# DD2090_4CAM_FFC_Power_Supply.net
KiCad netlist of a schematic drawn in Altium Designer
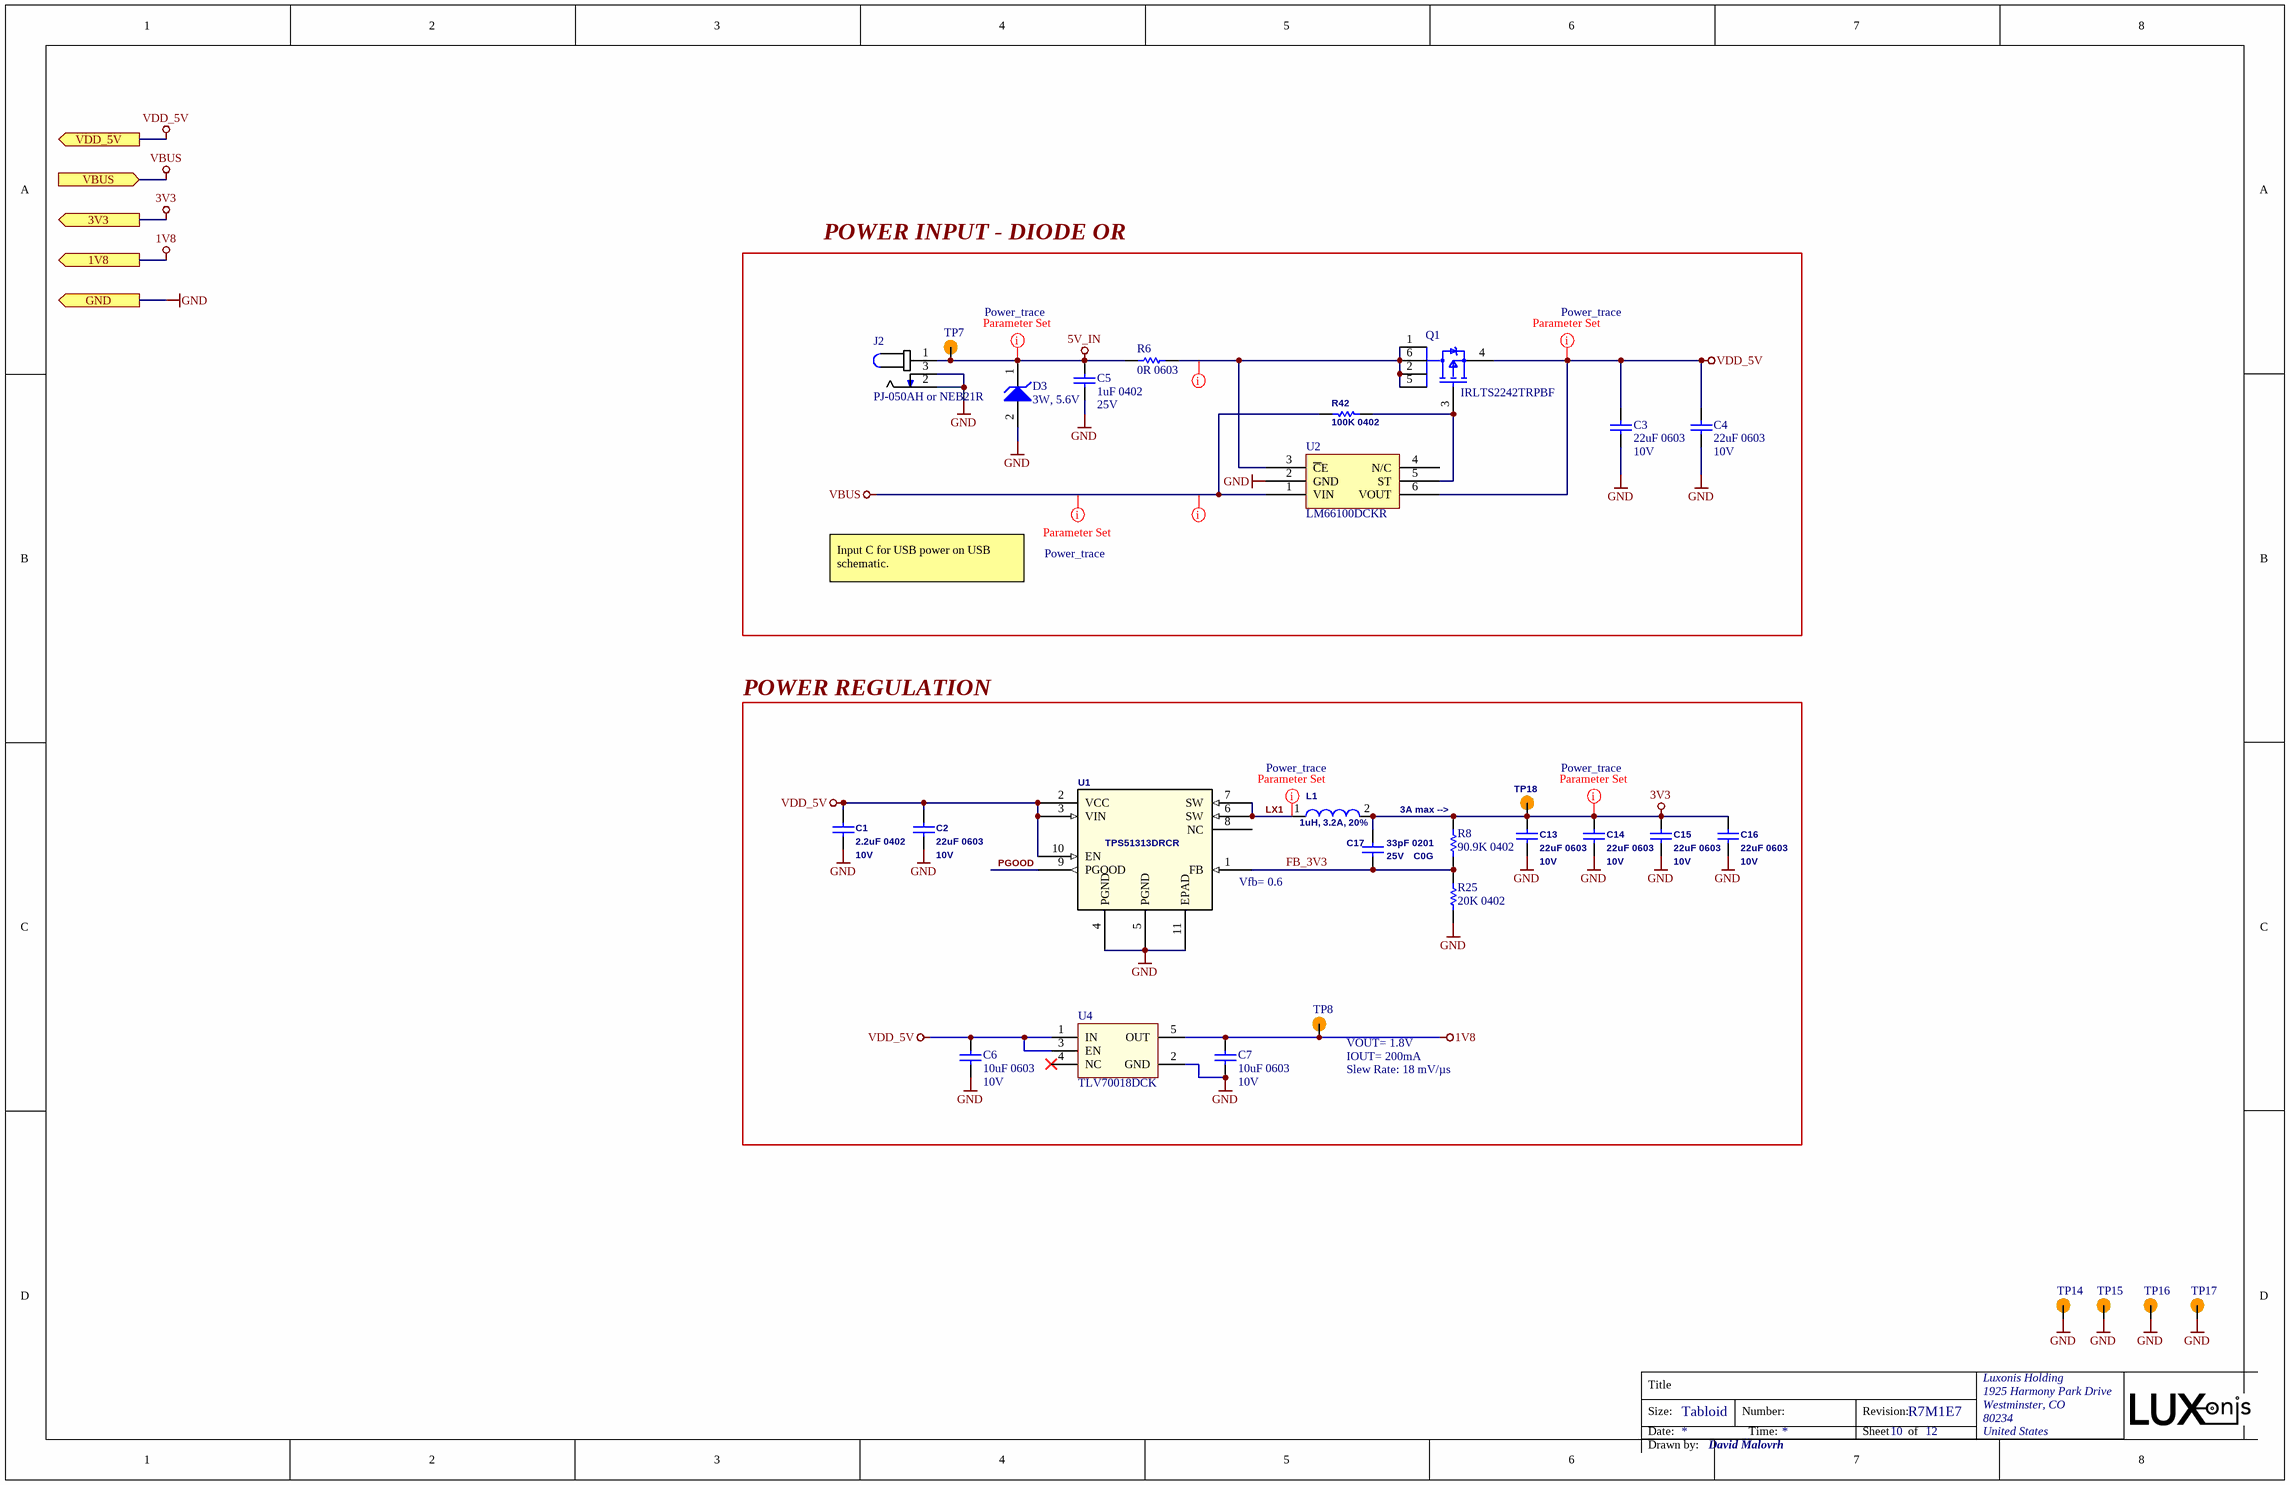
[diagram p0: DD2090_4CAM_FFC_Power_Supply.SchDoc]

(export (version "E")
  (design (tool "Eeschema 10.0.6"))
  (components
    (comp (ref "C1")
      (value "2.2uF 0402")
      (footprint "CAP_Altium_Vault_Generic:CAPC0402(1005)70_L")
      (description "CAP CER 2.2UF 10V X5R 0402 10%")
      (fields (field (name "TOLERANCE") "10%") (field (name "VOLTAGE RATING") "10V"))
      (libsource (lib "LuxonisMaster") (part "GRM155R61A225KE95D"))
    )
    (comp (ref "C2")
      (value "22uF 0603")
      (footprint "CAP_Altium_Vault_Generic:CAPC0603(1608)100_L")
      (description "CAP CER 22UF 10V X5R 0603 20%")
      (fields (field (name "TOLERANCE") "20%") (field (name "VOLTAGE RATING") "10V"))
      (libsource (lib "LuxonisMaster") (part "GRM188R61A226ME15D"))
    )
    (comp (ref "C3")
      (value "22uF 0603")
      (footprint "CAP_Altium_Vault_Generic:CAPC0603(1608)100_N")
      (description "CAP CER 22UF 10V X5R 0603 20%")
      (fields (field (name "TOLERANCE") "20%") (field (name "VOLTAGE RATING") "10V"))
      (libsource (lib "LuxonisMaster") (part "GRM188R61A226ME15D"))
    )
    (comp (ref "C4")
      (value "22uF 0603")
      (footprint "CAP_Altium_Vault_Generic:CAPC0603(1608)100_N")
      (description "CAP CER 22UF 10V X5R 0603 20%")
      (fields (field (name "TOLERANCE") "20%") (field (name "VOLTAGE RATING") "10V"))
      (libsource (lib "LuxonisMaster") (part "GRM188R61A226ME15D"))
    )
    (comp (ref "C5")
      (value "1uF 0402")
      (footprint "CAP_Altium_Vault_Generic:CAPC0402(1005)70_N")
      (description "CAP CER 1UF 25V X5R 0402 10%")
      (fields
        (field (name "TOLERANCE") "10%")
        (field (name "VOLTAGE") "25V")
        (field (name "VOLTAGE RATING") "25V")
      )
      (libsource (lib "LuxonisMaster") (part "GRM155R61E105KA12D"))
    )
    (comp (ref "C6")
      (value "10uF 0603")
      (footprint "CAP_Altium_Vault_Generic:CAPC0603(1608)100_L")
      (description "CAP CER 10UF 10V X5R 0603 20%")
      (fields (field (name "TOLERANCE") "20%") (field (name "VOLTAGE RATING") "10V"))
      (libsource (lib "LuxonisMaster") (part "GRM188R61A106ME69D"))
    )
    (comp (ref "C7")
      (value "10uF 0603")
      (footprint "CAP_Altium_Vault_Generic:CAPC0603(1608)100_L")
      (description "CAP CER 10UF 10V X5R 0603 20%")
      (fields (field (name "TOLERANCE") "20%") (field (name "VOLTAGE RATING") "10V"))
      (libsource (lib "LuxonisMaster") (part "GRM188R61A106ME69D"))
    )
    (comp (ref "C13")
      (value "22uF 0603")
      (footprint "CAP_Altium_Vault_Generic:CAPC0603(1608)100_L")
      (description "CAP CER 22UF 10V X5R 0603 20%")
      (fields (field (name "TOLERANCE") "20%") (field (name "VOLTAGE RATING") "10V"))
      (libsource (lib "LuxonisMaster") (part "GRM188R61A226ME15D"))
    )
    (comp (ref "C14")
      (value "22uF 0603")
      (footprint "CAP_Altium_Vault_Generic:CAPC0603(1608)100_L")
      (description "CAP CER 22UF 10V X5R 0603 20%")
      (fields (field (name "TOLERANCE") "20%") (field (name "VOLTAGE RATING") "10V"))
      (libsource (lib "LuxonisMaster") (part "GRM188R61A226ME15D"))
    )
    (comp (ref "C15")
      (value "22uF 0603")
      (footprint "CAP_Altium_Vault_Generic:CAPC0603(1608)100_L")
      (description "CAP CER 22UF 10V X5R 0603 20%")
      (fields (field (name "TOLERANCE") "20%") (field (name "VOLTAGE RATING") "10V"))
      (libsource (lib "LuxonisMaster") (part "GRM188R61A226ME15D"))
    )
    (comp (ref "C16")
      (value "22uF 0603")
      (footprint "CAP_Altium_Vault_Generic:CAPC0603(1608)100_L")
      (description "CAP CER 22UF 10V X5R 0603 20%")
      (fields (field (name "TOLERANCE") "20%") (field (name "VOLTAGE RATING") "10V"))
      (libsource (lib "LuxonisMaster") (part "GRM188R61A226ME15D"))
    )
    (comp (ref "C17")
      (value "33pF 0201")
      (footprint "CAP_Altium_Vault_Generic:CAPC0201(0603)33_L")
      (description "CAP CER 33PF 25V C0G/NP0 0201")
      (fields
        (field (name "TOLERANCE") "5%")
        (field (name "VOLTAGE RATING") "25V")
        (field (name "DIELECTRIC") "C0G")
      )
      (libsource (lib "LuxonisMaster") (part "GRM0335C1E330JA01D"))
    )
    (comp (ref "D3")
      (value "3W, 5.6V")
      (footprint "DM1092_R0M0E0:1SMB5919BT3G")
      (description "DIODE ZENER 5.6V 3W SMB")
      (fields (field (name "TOLERANCE") "5%"))
      (libsource (lib "DM1092_R0M0E0") (part "1SMB5919BT3G"))
    )
    (comp (ref "J2")
      (value "PJ-050AH or NEB21R")
      (footprint "LuxonisMaster:PJ-050AH/NEB21R_COMBO")
      (description "CONN POWER PIN 2 POS RA PTH Barrel jack 2.1mm x 5.5mm combo footprint")
      (libsource (lib "LuxonisMaster") (part "PJ-050AH/NEB21R_COMBO"))
    )
    (comp (ref "L1")
      (value "1uH, 3.2A, 20%")
      (footprint "LuxonisMaster:DFE252012P-1R0M=P2")
      (description "FIXED IND 1UH 3.2A 42 MOHM SMD")
      (fields
        (field (name "MANUFACTURER") "Murata")
        (field (name "MANUFACTURER PART NUMBER") "DFE252012P-1R0M=P2")
      )
      (libsource (lib "LuxonisMaster") (part "DFE252012P-1R0M=P2"))
    )
    (comp (ref "Q1")
      (value "IRLTS2242TRPBF")
      (footprint "TSOP-6-MFG")
      (description "MOSFET P-CH 20V 6.9A 6TSOP")
      (libsource (lib "Luxonis LLC") (part "IRLTS2242TRPBF"))
    )
    (comp (ref "R6")
      (value "0R 0603")
      (footprint "RES_Altium_Vault_Generic:RESC0603(1608)_N")
      (fields (field (name "TOLERANCE") "5%"))
      (libsource (lib "LuxonisMaster") (part "CRCW06030000Z0EA"))
    )
    (comp (ref "R8")
      (value "90.9K 0402")
      (footprint "RES_Altium_Vault_Generic:RESC0402(1005)_L")
      (description "RES SMD 90.9K OHM 1% 1/16W 0402")
      (fields (field (name "TOLERANCE") "1%"))
      (libsource (lib "LuxonisMaster") (part "CRCW040290K9FKED"))
    )
    (comp (ref "R25")
      (value "20K 0402")
      (footprint "RES_Altium_Vault_Generic:RESC0402(1005)_L")
      (fields
        (field (name "MANUFACTURER") "Yageo")
        (field (name "MANUFACTURER PART NUMBER") "RC0402FR-0720KL")
        (field (name "TOLERANCE") "1%")
      )
      (libsource (lib "LuxonisMaster") (part "RC0402FR-0720KL"))
    )
    (comp (ref "R42")
      (value "100K 0402")
      (footprint "RES_Altium_Vault_Generic:RESC0402(1005)_L")
      (description "RES SMD 100K OHM 1% 1/16W 0402")
      (fields (field (name "TOLERANCE") "1%"))
      (libsource (lib "LuxonisMaster") (part "RC0402FR-07100KL"))
    )
    (comp (ref "TP7")
      (value "TP100_200_NS")
      (footprint "LuxonisMaster:TP100_200_NS")
      (libsource (lib "LuxonisMaster") (part "TEST_POINT"))
    )
    (comp (ref "TP8")
      (value "TP100_200_NS")
      (footprint "LuxonisMaster:TP100_200_NS")
      (libsource (lib "LuxonisMaster") (part "TEST_POINT"))
    )
    (comp (ref "TP14")
      (value "TP100_200_NS")
      (footprint "LuxonisMaster:TP100_200_NS")
      (libsource (lib "LuxonisMaster") (part "TEST_POINT"))
    )
    (comp (ref "TP15")
      (value "TP100_200_NS")
      (footprint "LuxonisMaster:TP100_200_NS")
      (libsource (lib "LuxonisMaster") (part "TEST_POINT"))
    )
    (comp (ref "TP16")
      (value "TP100_200_NS")
      (footprint "LuxonisMaster:TP100_200_NS")
      (libsource (lib "LuxonisMaster") (part "TEST_POINT"))
    )
    (comp (ref "TP17")
      (value "TP100_200_NS")
      (footprint "LuxonisMaster:TP100_200_NS")
      (libsource (lib "LuxonisMaster") (part "TEST_POINT"))
    )
    (comp (ref "TP18")
      (value "TP075_150_NS")
      (footprint "LuxonisMaster:TP075_150_NS")
      (libsource (lib "LuxonisMaster") (part "TEST_POINT"))
    )
    (comp (ref "U1")
      (value "TPS51313DRCR")
      (footprint "VSON-TPS51313DRCR")
      (description "Switching Regulator, Voltage-mode, 3A, 1000kHz Switching Freq-Max, PDSO10")
      (libsource (lib "LuxonisMaster") (part "TPS51313DRCR"))
    )
    (comp (ref "U2")
      (value "LM66100DCKR")
      (footprint "LM66100DCKR")
      (description "IC OR CTRLR IDEAL DIODE SC70-6")
      (libsource (lib "Luxonis LLC") (part "LM66100DCKR"))
    )
    (comp (ref "U4")
      (value "TLV70018DCK")
      (footprint "LuxonisMaster:TLV70018DCK")
      (description "IC REG LINEAR 1.8V 200MA SC70-5 Linear Voltage Regulator IC  1 Output  200mA SC-70-5")
      (libsource (lib "LuxonisMaster") (part "TLV70018DCK"))
    )
  )
  (nets
    (net (code "1") (name "/FB_3V3") (class "Default")
      (node (ref "C17") (pin "1") (pinfunction "1_1") (pintype "passive"))
      (node (ref "R25") (pin "2") (pinfunction "2_2") (pintype "passive"))
      (node (ref "R8") (pin "1") (pinfunction "1_1") (pintype "passive"))
      (node (ref "U1") (pin "1") (pinfunction "FB_1") (pintype "input"))
    )
    (net (code "2") (name "/LX1") (class "Default")
      (node (ref "L1") (pin "1") (pinfunction "1_1") (pintype "passive"))
      (node (ref "U1") (pin "6") (pinfunction "SW_6") (pintype "input"))
      (node (ref "U1") (pin "7") (pinfunction "SW_7") (pintype "input"))
    )
    (net (code "3") (name "/PGOOD") (class "Default")
      (node (ref "U1") (pin "9") (pinfunction "PGOOD_9") (pintype "output"))
    )
    (net (code "4") (name "1V8") (class "Default")
      (node (ref "C7") (pin "2") (pinfunction "2_2") (pintype "passive"))
      (node (ref "TP8") (pin "1") (pintype "passive"))
      (node (ref "U4") (pin "5") (pinfunction "OUT_5") (pintype "passive"))
    )
    (net (code "5") (name "3V3") (class "Default")
      (node (ref "C13") (pin "1") (pinfunction "1_1") (pintype "passive"))
      (node (ref "C14") (pin "1") (pinfunction "1_1") (pintype "passive"))
      (node (ref "C15") (pin "1") (pinfunction "1_1") (pintype "passive"))
      (node (ref "C16") (pin "1") (pinfunction "1_1") (pintype "passive"))
      (node (ref "C17") (pin "2") (pinfunction "2_2") (pintype "passive"))
      (node (ref "L1") (pin "2") (pinfunction "2_2") (pintype "passive"))
      (node (ref "R8") (pin "2") (pinfunction "2_2") (pintype "passive"))
      (node (ref "TP18") (pin "1") (pintype "passive"))
    )
    (net (code "6") (name "5V_IN") (class "Default")
      (node (ref "C5") (pin "2") (pinfunction "2_2") (pintype "passive"))
      (node (ref "D3") (pin "1") (pinfunction "K_1") (pintype "passive"))
      (node (ref "J2") (pin "1") (pinfunction "1_1") (pintype "passive"))
      (node (ref "R6") (pin "1") (pinfunction "1_1") (pintype "passive"))
      (node (ref "TP7") (pin "1") (pintype "passive"))
    )
    (net (code "7") (name "GND") (class "Default")
      (node (ref "C1") (pin "2") (pinfunction "2_2") (pintype "passive"))
      (node (ref "C13") (pin "2") (pinfunction "2_2") (pintype "passive"))
      (node (ref "C14") (pin "2") (pinfunction "2_2") (pintype "passive"))
      (node (ref "C15") (pin "2") (pinfunction "2_2") (pintype "passive"))
      (node (ref "C16") (pin "2") (pinfunction "2_2") (pintype "passive"))
      (node (ref "C2") (pin "2") (pinfunction "2_2") (pintype "passive"))
      (node (ref "C3") (pin "1") (pinfunction "1_1") (pintype "passive"))
      (node (ref "C4") (pin "1") (pinfunction "1_1") (pintype "passive"))
      (node (ref "C5") (pin "1") (pinfunction "1_1") (pintype "passive"))
      (node (ref "C6") (pin "1") (pinfunction "1_1") (pintype "passive"))
      (node (ref "C7") (pin "1") (pinfunction "1_1") (pintype "passive"))
      (node (ref "D3") (pin "2") (pinfunction "A_2") (pintype "passive"))
      (node (ref "J2") (pin "2") (pinfunction "2_2") (pintype "passive"))
      (node (ref "J2") (pin "3") (pinfunction "3_3") (pintype "passive"))
      (node (ref "R25") (pin "1") (pinfunction "1_1") (pintype "passive"))
      (node (ref "TP14") (pin "1") (pintype "passive"))
      (node (ref "TP15") (pin "1") (pintype "passive"))
      (node (ref "TP16") (pin "1") (pintype "passive"))
      (node (ref "TP17") (pin "1") (pintype "passive"))
      (node (ref "U1") (pin "11") (pinfunction "EPAD_11") (pintype "passive"))
      (node (ref "U1") (pin "4") (pinfunction "PGND_4") (pintype "power_in"))
      (node (ref "U1") (pin "5") (pinfunction "PGND_5") (pintype "power_in"))
      (node (ref "U2") (pin "2") (pinfunction "GND_2") (pintype "passive"))
      (node (ref "U4") (pin "2") (pinfunction "GND_2") (pintype "passive"))
    )
    (net (code "8") (name "Net-(Q1-G)") (class "Default")
      (node (ref "Q1") (pin "3") (pinfunction "G_3") (pintype "passive"))
      (node (ref "R42") (pin "2") (pinfunction "2_2") (pintype "passive"))
      (node (ref "U2") (pin "5") (pinfunction "ST_5") (pintype "passive"))
    )
    (net (code "9") (name "Net-(U2-~{C}E)") (class "Default")
      (node (ref "Q1") (pin "1") (pinfunction "D_1") (pintype "passive"))
      (node (ref "Q1") (pin "2") (pinfunction "D_2") (pintype "passive"))
      (node (ref "Q1") (pin "5") (pinfunction "D_5") (pintype "passive"))
      (node (ref "Q1") (pin "6") (pinfunction "D_6") (pintype "passive"))
      (node (ref "R6") (pin "2") (pinfunction "2_2") (pintype "passive"))
      (node (ref "U2") (pin "3") (pinfunction "~{C}E_3") (pintype "passive"))
    )
    (net (code "10") (name "VBUS") (class "Default")
      (node (ref "R42") (pin "1") (pinfunction "1_1") (pintype "passive"))
      (node (ref "U2") (pin "1") (pinfunction "VIN_1") (pintype "passive"))
    )
    (net (code "11") (name "VDD_5V") (class "Default")
      (node (ref "C1") (pin "1") (pinfunction "1_1") (pintype "passive"))
      (node (ref "C2") (pin "1") (pinfunction "1_1") (pintype "passive"))
      (node (ref "C3") (pin "2") (pinfunction "2_2") (pintype "passive"))
      (node (ref "C4") (pin "2") (pinfunction "2_2") (pintype "passive"))
      (node (ref "C6") (pin "2") (pinfunction "2_2") (pintype "passive"))
      (node (ref "Q1") (pin "4") (pinfunction "S_4") (pintype "passive"))
      (node (ref "U1") (pin "10") (pinfunction "EN_10") (pintype "input"))
      (node (ref "U1") (pin "2") (pinfunction "VCC_2") (pintype "power_in"))
      (node (ref "U1") (pin "3") (pinfunction "VIN_3") (pintype "input"))
      (node (ref "U2") (pin "6") (pinfunction "VOUT_6") (pintype "passive"))
      (node (ref "U4") (pin "1") (pinfunction "IN_1") (pintype "passive"))
      (node (ref "U4") (pin "3") (pinfunction "EN_3") (pintype "passive"))
    )
    (net (code "12") (name "unconnected-(U1-NC-Pad8)") (class "Default")
      (node (ref "U1") (pin "8") (pinfunction "NC_8") (pintype "passive"))
    )
    (net (code "13") (name "unconnected-(U2-N{slash}C-Pad4)") (class "Default")
      (node (ref "U2") (pin "4") (pinfunction "N/C_4") (pintype "passive"))
    )
    (net (code "14") (name "unconnected-(U4-NC-Pad4)") (class "Default")
      (node (ref "U4") (pin "4") (pinfunction "NC_4") (pintype "passive+no_connect"))
    )
  )
)
